# stm32hw03.net
KiCad netlist of a schematic drawn in EAGLE
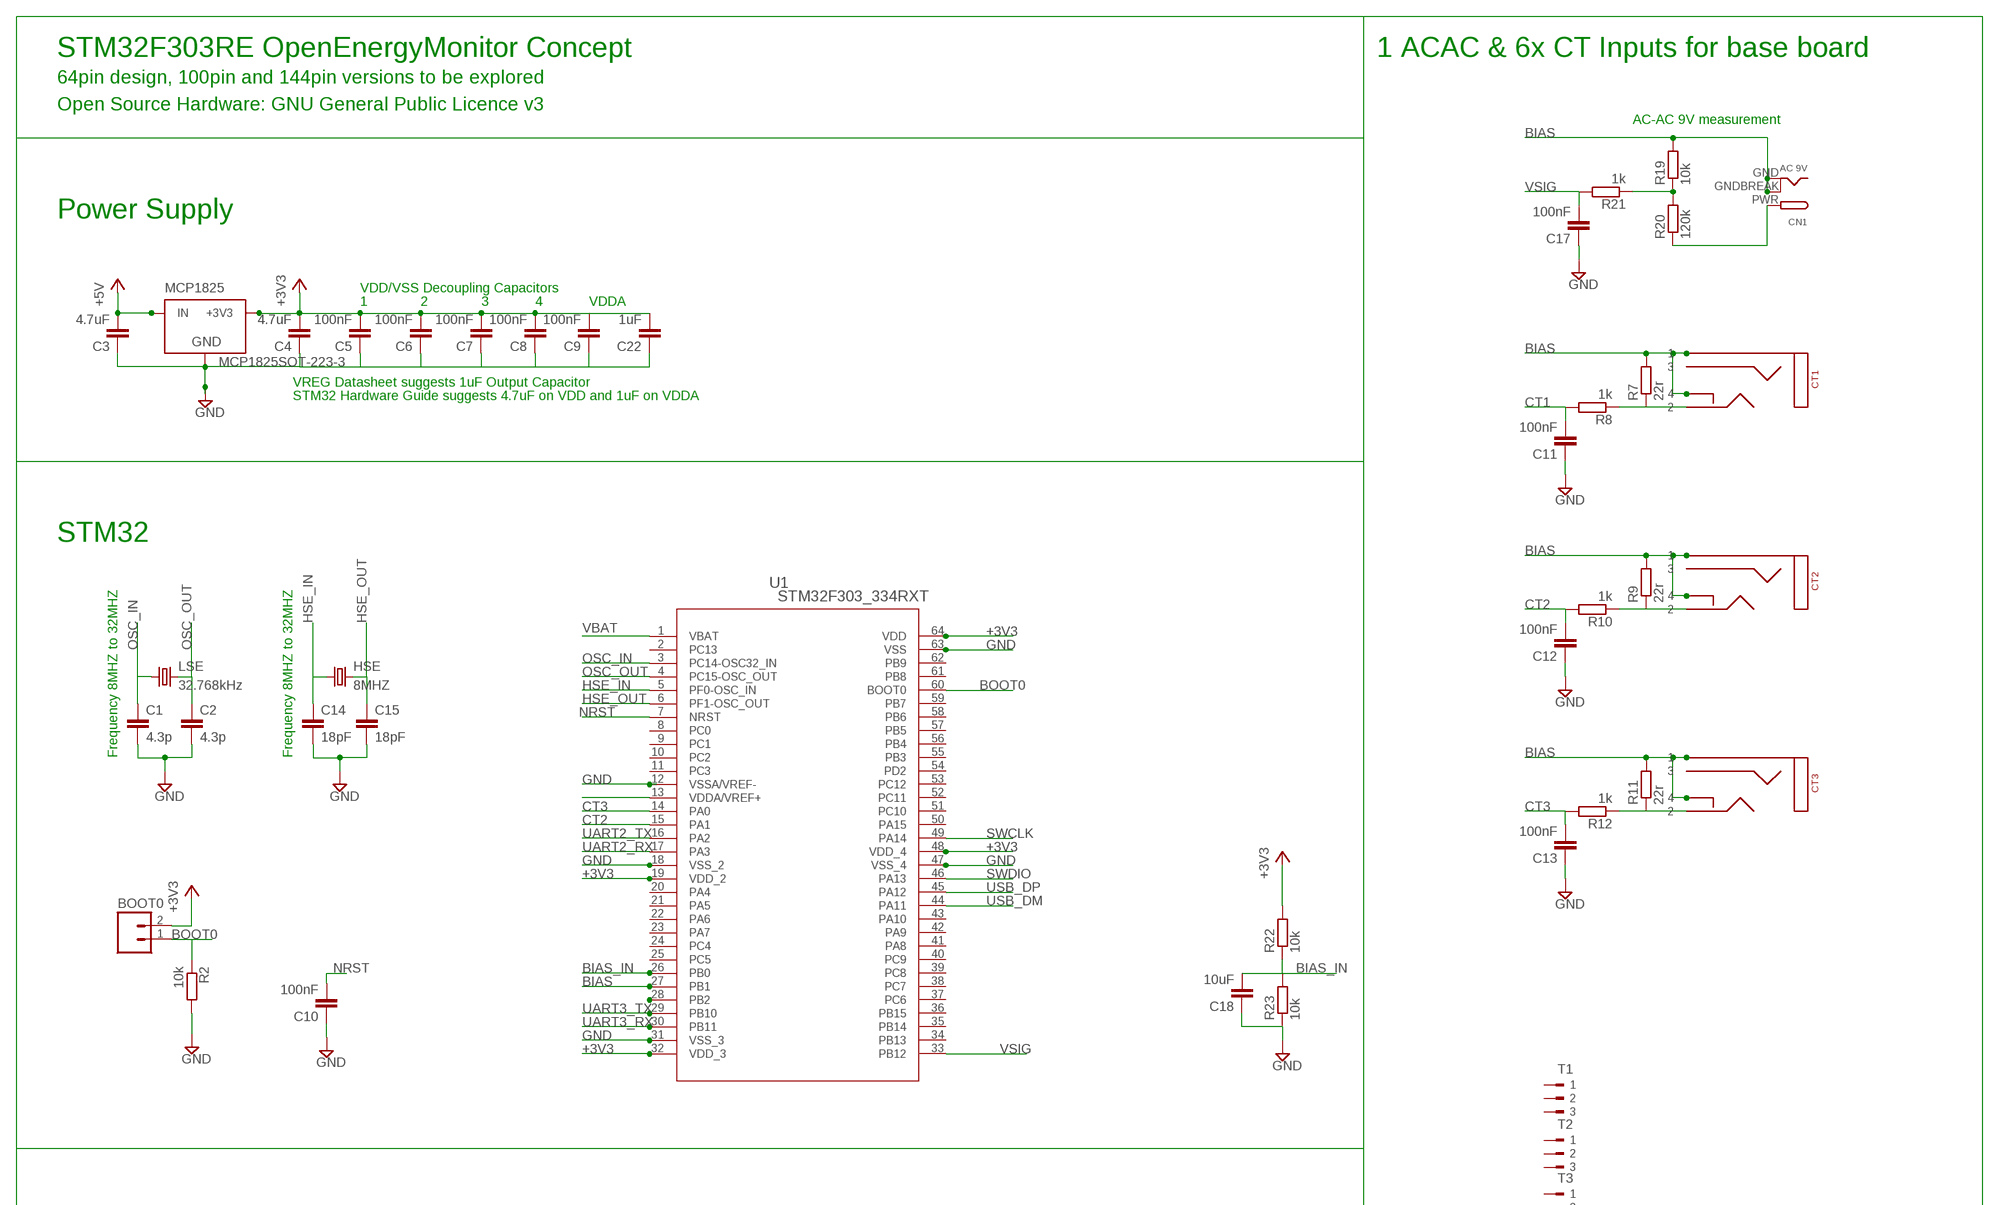
[diagram p0: schematic, sheet 1, part 1 of 2]
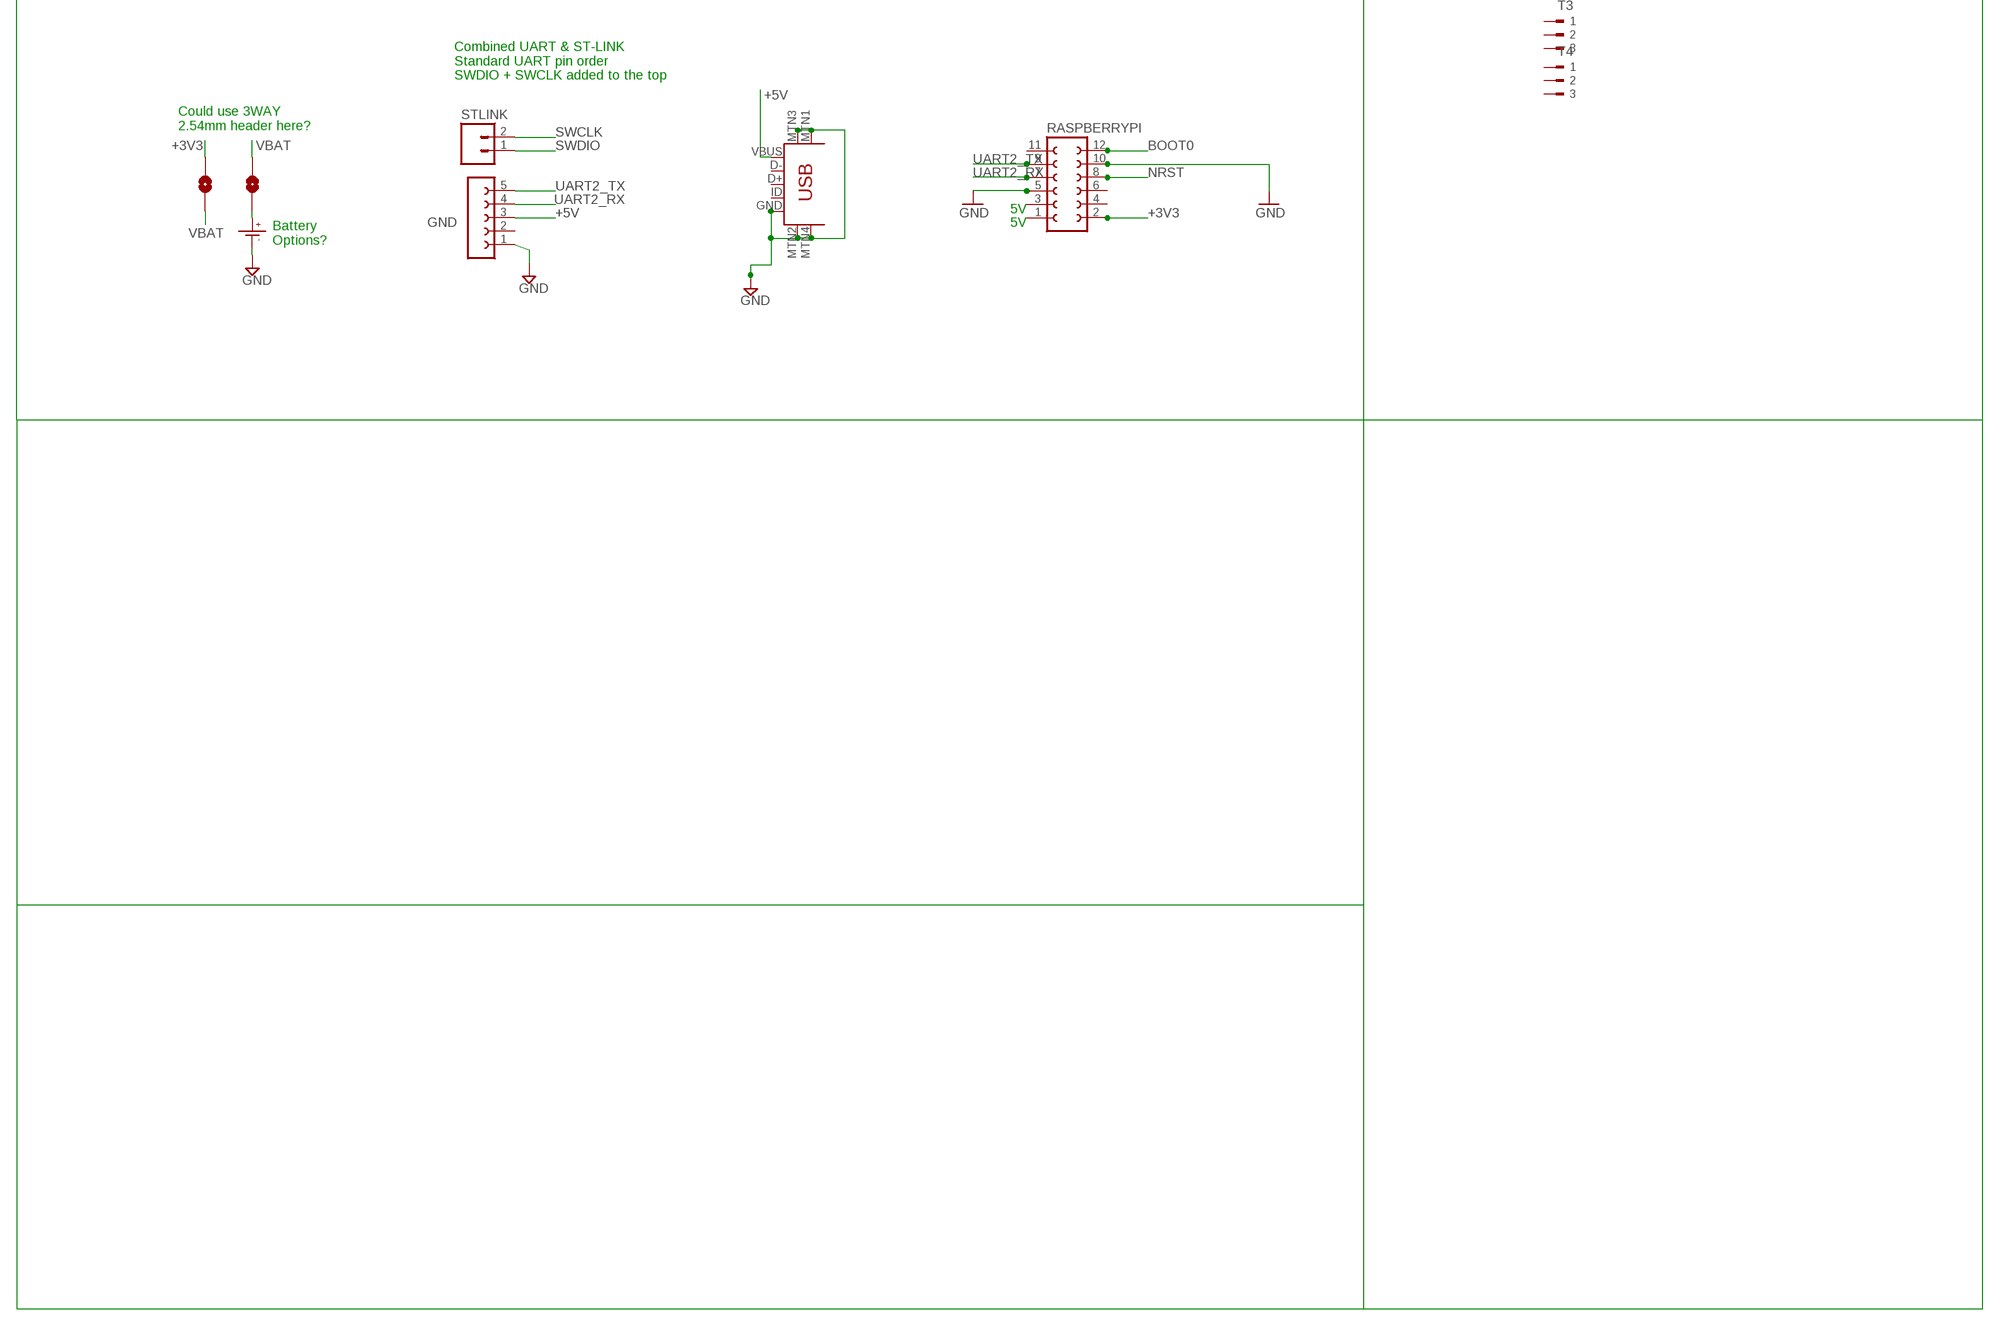
[diagram p1: schematic, sheet 1, part 2 of 2]

(export (version "E")
  (design (tool "Eeschema 10.0.6"))
  (components
    (comp (ref "3V3")
      (value "SOLDERJUMPERNO")
      (footprint "eagle-import:SJ_2S-NO")
      (libsource (lib "eagle-import") (part "SOLDERJUMPERNO"))
    )
    (comp (ref "BATTERY")
      (value "SOLDERJUMPERNO")
      (footprint "eagle-import:SJ_2S-NO")
      (libsource (lib "eagle-import") (part "SOLDERJUMPERNO"))
    )
    (comp (ref "BOOT0")
      (value "M02PTH")
      (footprint "eagle-import:1X02")
      (libsource (lib "eagle-import") (part "M02PTH"))
    )
    (comp (ref "C1")
      (value "4.3p")
      (footprint "eagle-import:C0603")
      (libsource (lib "eagle-import") (part "C-EUC0603"))
    )
    (comp (ref "C2")
      (value "4.3p")
      (footprint "eagle-import:C0603")
      (libsource (lib "eagle-import") (part "C-EUC0603"))
    )
    (comp (ref "C3")
      (value "4.7uF")
      (footprint "eagle-import:C0603")
      (libsource (lib "eagle-import") (part "C-EUC0603"))
    )
    (comp (ref "C4")
      (value "4.7uF")
      (footprint "eagle-import:C0603")
      (libsource (lib "eagle-import") (part "C-EUC0603"))
    )
    (comp (ref "C5")
      (value "100nF")
      (footprint "eagle-import:C0603")
      (libsource (lib "eagle-import") (part "C-EUC0603"))
    )
    (comp (ref "C6")
      (value "100nF")
      (footprint "eagle-import:C0603")
      (libsource (lib "eagle-import") (part "C-EUC0603"))
    )
    (comp (ref "C7")
      (value "100nF")
      (footprint "eagle-import:C0603")
      (libsource (lib "eagle-import") (part "C-EUC0603"))
    )
    (comp (ref "C8")
      (value "100nF")
      (footprint "eagle-import:C0603")
      (libsource (lib "eagle-import") (part "C-EUC0603"))
    )
    (comp (ref "C9")
      (value "100nF")
      (footprint "eagle-import:C0603")
      (libsource (lib "eagle-import") (part "C-EUC0603"))
    )
    (comp (ref "C10")
      (value "100nF")
      (footprint "eagle-import:C0603")
      (libsource (lib "eagle-import") (part "C-EUC0603"))
    )
    (comp (ref "C11")
      (value "100nF")
      (footprint "eagle-import:C0603")
      (libsource (lib "eagle-import") (part "C-EUC0603"))
    )
    (comp (ref "C12")
      (value "100nF")
      (footprint "eagle-import:C0603")
      (libsource (lib "eagle-import") (part "C-EUC0603"))
    )
    (comp (ref "C13")
      (value "100nF")
      (footprint "eagle-import:C0603")
      (libsource (lib "eagle-import") (part "C-EUC0603"))
    )
    (comp (ref "C14")
      (value "18pF")
      (footprint "eagle-import:C0603")
      (libsource (lib "eagle-import") (part "C-EUC0603"))
    )
    (comp (ref "C15")
      (value "18pF")
      (footprint "eagle-import:C0603")
      (libsource (lib "eagle-import") (part "C-EUC0603"))
    )
    (comp (ref "C17")
      (value "100nF")
      (footprint "eagle-import:C0603")
      (libsource (lib "eagle-import") (part "C-EUC0603"))
    )
    (comp (ref "C18")
      (value "10uF")
      (footprint "eagle-import:C0603")
      (libsource (lib "eagle-import") (part "C-EUC0603"))
    )
    (comp (ref "C22")
      (value "1uF")
      (footprint "eagle-import:C0603")
      (libsource (lib "eagle-import") (part "C-EUC0603"))
    )
    (comp (ref "CN1")
      (value "AC 9V")
      (footprint "eagle-import:DCJACK_2MM_PTH")
      (libsource (lib "eagle-import") (part "DCBARRELPTH"))
    )
    (comp (ref "CR1220")
      (value "CR1220SMD")
      (footprint "eagle-import:CR1220SMD")
      (fields (field (name "MPN") "Harwin S8411-45R"))
      (libsource (lib "eagle-import") (part "CR1220SMD"))
    )
    (comp (ref "CT1")
      (value "STEREO_SMD")
      (footprint "eagle-import:STEREO_SMT")
      (libsource (lib "eagle-import") (part "STEREO_SMD"))
    )
    (comp (ref "CT2")
      (value "STEREO_SMD")
      (footprint "eagle-import:STEREO_SMT")
      (libsource (lib "eagle-import") (part "STEREO_SMD"))
    )
    (comp (ref "CT3")
      (value "STEREO_SMD")
      (footprint "eagle-import:STEREO_SMT")
      (libsource (lib "eagle-import") (part "STEREO_SMD"))
    )
    (comp (ref "GND")
      (value "UART")
      (footprint "eagle-import:FE05-1")
      (libsource (lib "eagle-import") (part "FE05-1"))
    )
    (comp (ref "HSE")
      (value "8MHZ")
      (footprint "eagle-import:CTS406")
      (libsource (lib "eagle-import") (part "CRYSTALCTS406"))
    )
    (comp (ref "LSE")
      (value "32.768kHz")
      (footprint "eagle-import:MC-306")
      (fields (field (name "MPN") "MC-306 60.0KHZ  100PPM ,12.5PF"))
      (libsource (lib "eagle-import") (part "MC-306"))
    )
    (comp (ref "MCP1825")
      (value "MCP1825SOT-223-3")
      (footprint "eagle-import:SOT-223")
      (libsource (lib "eagle-import") (part "MCP1825SOT-223-3"))
    )
    (comp (ref "R2")
      (value "10k")
      (footprint "eagle-import:R0603")
      (libsource (lib "eagle-import") (part "R-EU_R0603"))
    )
    (comp (ref "R7")
      (value "22r")
      (footprint "eagle-import:R0603")
      (libsource (lib "eagle-import") (part "R-EU_R0603"))
    )
    (comp (ref "R8")
      (value "1k")
      (footprint "eagle-import:R0603")
      (libsource (lib "eagle-import") (part "R-EU_R0603"))
    )
    (comp (ref "R9")
      (value "22r")
      (footprint "eagle-import:R0603")
      (libsource (lib "eagle-import") (part "R-EU_R0603"))
    )
    (comp (ref "R10")
      (value "1k")
      (footprint "eagle-import:R0603")
      (libsource (lib "eagle-import") (part "R-EU_R0603"))
    )
    (comp (ref "R11")
      (value "22r")
      (footprint "eagle-import:R0603")
      (libsource (lib "eagle-import") (part "R-EU_R0603"))
    )
    (comp (ref "R12")
      (value "1k")
      (footprint "eagle-import:R0603")
      (libsource (lib "eagle-import") (part "R-EU_R0603"))
    )
    (comp (ref "R19")
      (value "10k")
      (footprint "eagle-import:R0603")
      (libsource (lib "eagle-import") (part "R-EU_R0603"))
    )
    (comp (ref "R20")
      (value "120k")
      (footprint "eagle-import:R0603")
      (libsource (lib "eagle-import") (part "R-EU_R0603"))
    )
    (comp (ref "R21")
      (value "1k")
      (footprint "eagle-import:R0603")
      (libsource (lib "eagle-import") (part "R-EU_R0603"))
    )
    (comp (ref "R22")
      (value "10k")
      (footprint "eagle-import:R0603")
      (libsource (lib "eagle-import") (part "R-EU_R0603"))
    )
    (comp (ref "R23")
      (value "10k")
      (footprint "eagle-import:R0603")
      (libsource (lib "eagle-import") (part "R-EU_R0603"))
    )
    (comp (ref "RASPBERRYPI")
      (value "FE06-2")
      (footprint "eagle-import:FE06-2")
      (libsource (lib "eagle-import") (part "FE06-2"))
    )
    (comp (ref "STLINK")
      (value "M02PTH")
      (footprint "eagle-import:1X02")
      (libsource (lib "eagle-import") (part "M02PTH"))
    )
    (comp (ref "T1")
      (value "180-3")
      (footprint "eagle-import:180-3")
      (libsource (lib "eagle-import") (part "180-3"))
    )
    (comp (ref "T2")
      (value "180-3")
      (footprint "eagle-import:180-3")
      (libsource (lib "eagle-import") (part "180-3"))
    )
    (comp (ref "T3")
      (value "180-3")
      (footprint "eagle-import:180-3")
      (libsource (lib "eagle-import") (part "180-3"))
    )
    (comp (ref "T4")
      (value "180-3")
      (footprint "eagle-import:180-3")
      (libsource (lib "eagle-import") (part "180-3"))
    )
    (comp (ref "U$10")
      (value "USB-MINIB-5PIN")
      (footprint "eagle-import:USB-MINIB-CISECO")
      (libsource (lib "eagle-import") (part "USB-MINIB-5PIN"))
    )
    (comp (ref "U1")
      (value "STM32F303_334RXT")
      (footprint "eagle-import:LQFP64-10X10MM")
      (fields (field (name "MANUFACTURER_PART_NUMBER") "stm32f303_334rxt"))
      (libsource (lib "eagle-import") (part "STM32F303_334RXT"))
    )
  )
  (nets
    (net (code "1") (name "+3V3") (class "Default")
      (node (ref "3V3") (pin "1") (pinfunction "1_1") (pintype "passive"))
      (node (ref "BOOT0") (pin "2") (pinfunction "2_2") (pintype "passive"))
      (node (ref "C22") (pin "2") (pinfunction "2_2") (pintype "passive"))
      (node (ref "C4") (pin "2") (pinfunction "2_2") (pintype "passive"))
      (node (ref "C5") (pin "2") (pinfunction "2_2") (pintype "passive"))
      (node (ref "C6") (pin "2") (pinfunction "2_2") (pintype "passive"))
      (node (ref "C7") (pin "2") (pinfunction "2_2") (pintype "passive"))
      (node (ref "C8") (pin "2") (pinfunction "2_2") (pintype "passive"))
      (node (ref "C9") (pin "2") (pinfunction "2_2") (pintype "passive"))
      (node (ref "MCP1825") (pin "3") (pinfunction "+3V3_3") (pintype "power_in"))
      (node (ref "R22") (pin "2") (pinfunction "2_2") (pintype "passive"))
      (node (ref "RASPBERRYPI") (pin "2") (pinfunction "2_2") (pintype "passive"))
      (node (ref "U1") (pin "13") (pinfunction "VDDA/VREF+_13") (pintype "power_in"))
      (node (ref "U1") (pin "19") (pinfunction "VDD_2_19") (pintype "power_in"))
      (node (ref "U1") (pin "32") (pinfunction "VDD_3_32") (pintype "power_in"))
      (node (ref "U1") (pin "48") (pinfunction "VDD_4_48") (pintype "power_in"))
      (node (ref "U1") (pin "64") (pinfunction "VDD_64") (pintype "power_in"))
    )
    (net (code "2") (name "+5V") (class "Default")
      (node (ref "C3") (pin "2") (pinfunction "2_2") (pintype "passive"))
      (node (ref "GND") (pin "3") (pinfunction "3_3") (pintype "passive"))
      (node (ref "MCP1825") (pin "1") (pinfunction "IN_1") (pintype "power_in"))
      (node (ref "U$10") (pin "VBUS") (pinfunction "VBUS_VBUS") (pintype "bidirectional"))
    )
    (net (code "3") (name "/BIAS") (class "Default")
      (node (ref "CN1") (pin "GND") (pinfunction "GND_GND") (pintype "power_in"))
      (node (ref "CN1") (pin "GNDBREAK") (pinfunction "GNDBREAK_GNDBREAK") (pintype "power_in"))
      (node (ref "CT1") (pin "P$1") (pinfunction "1_P$1") (pintype "bidirectional"))
      (node (ref "CT1") (pin "P$4") (pinfunction "4_P$4") (pintype "bidirectional"))
      (node (ref "CT2") (pin "P$1") (pinfunction "1_P$1") (pintype "bidirectional"))
      (node (ref "CT2") (pin "P$4") (pinfunction "4_P$4") (pintype "bidirectional"))
      (node (ref "CT3") (pin "P$1") (pinfunction "1_P$1") (pintype "bidirectional"))
      (node (ref "CT3") (pin "P$4") (pinfunction "4_P$4") (pintype "bidirectional"))
      (node (ref "R11") (pin "2") (pinfunction "2_2") (pintype "passive"))
      (node (ref "R19") (pin "2") (pinfunction "2_2") (pintype "passive"))
      (node (ref "R7") (pin "2") (pinfunction "2_2") (pintype "passive"))
      (node (ref "R9") (pin "2") (pinfunction "2_2") (pintype "passive"))
      (node (ref "U1") (pin "27") (pinfunction "PB1_27") (pintype "bidirectional"))
    )
    (net (code "4") (name "/BIAS_IN") (class "Default")
      (node (ref "C18") (pin "2") (pinfunction "2_2") (pintype "passive"))
      (node (ref "R22") (pin "1") (pinfunction "1_1") (pintype "passive"))
      (node (ref "R23") (pin "2") (pinfunction "2_2") (pintype "passive"))
      (node (ref "U1") (pin "26") (pinfunction "PB0_26") (pintype "bidirectional"))
    )
    (net (code "5") (name "/BOOT0") (class "Default")
      (node (ref "BOOT0") (pin "1") (pinfunction "1_1") (pintype "passive"))
      (node (ref "R2") (pin "1") (pinfunction "1_1") (pintype "passive"))
      (node (ref "RASPBERRYPI") (pin "12") (pinfunction "12_12") (pintype "passive"))
      (node (ref "U1") (pin "60") (pinfunction "BOOT0_60") (pintype "input"))
    )
    (net (code "6") (name "/CT1") (class "Default")
      (node (ref "C11") (pin "2") (pinfunction "2_2") (pintype "passive"))
      (node (ref "R8") (pin "2") (pinfunction "2_2") (pintype "passive"))
    )
    (net (code "7") (name "/CT2") (class "Default")
      (node (ref "C12") (pin "2") (pinfunction "2_2") (pintype "passive"))
      (node (ref "R10") (pin "2") (pinfunction "2_2") (pintype "passive"))
      (node (ref "U1") (pin "15") (pinfunction "PA1_15") (pintype "bidirectional"))
    )
    (net (code "8") (name "/CT3") (class "Default")
      (node (ref "C13") (pin "2") (pinfunction "2_2") (pintype "passive"))
      (node (ref "R12") (pin "2") (pinfunction "2_2") (pintype "passive"))
      (node (ref "U1") (pin "14") (pinfunction "PA0_14") (pintype "bidirectional"))
    )
    (net (code "9") (name "/HSE_IN") (class "Default")
      (node (ref "C14") (pin "1") (pinfunction "1_1") (pintype "passive"))
      (node (ref "HSE") (pin "1") (pinfunction "1_1") (pintype "passive"))
      (node (ref "U1") (pin "5") (pinfunction "PF0-OSC_IN_5") (pintype "bidirectional"))
    )
    (net (code "10") (name "/HSE_OUT") (class "Default")
      (node (ref "C15") (pin "1") (pinfunction "1_1") (pintype "passive"))
      (node (ref "HSE") (pin "3") (pinfunction "2_3") (pintype "passive"))
      (node (ref "U1") (pin "6") (pinfunction "PF1-OSC_OUT_6") (pintype "bidirectional"))
    )
    (net (code "11") (name "/NRST") (class "Default")
      (node (ref "C10") (pin "2") (pinfunction "2_2") (pintype "passive"))
      (node (ref "RASPBERRYPI") (pin "8") (pinfunction "8_8") (pintype "passive"))
      (node (ref "U1") (pin "7") (pinfunction "NRST_7") (pintype "bidirectional"))
    )
    (net (code "12") (name "/OSC_IN") (class "Default")
      (node (ref "C1") (pin "1") (pinfunction "1_1") (pintype "passive"))
      (node (ref "LSE") (pin "1") (pinfunction "1_1") (pintype "passive"))
      (node (ref "U1") (pin "3") (pinfunction "PC14-OSC32_IN_3") (pintype "bidirectional"))
    )
    (net (code "13") (name "/OSC_OUT") (class "Default")
      (node (ref "C2") (pin "1") (pinfunction "1_1") (pintype "passive"))
      (node (ref "LSE") (pin "4") (pinfunction "2_4") (pintype "passive"))
      (node (ref "U1") (pin "4") (pinfunction "PC15-OSC_OUT_4") (pintype "bidirectional"))
    )
    (net (code "14") (name "/SWCLK") (class "Default")
      (node (ref "STLINK") (pin "2") (pinfunction "2_2") (pintype "passive"))
      (node (ref "U1") (pin "49") (pinfunction "PA14_49") (pintype "bidirectional"))
    )
    (net (code "15") (name "/SWDIO") (class "Default")
      (node (ref "STLINK") (pin "1") (pinfunction "1_1") (pintype "passive"))
      (node (ref "U1") (pin "46") (pinfunction "PA13_46") (pintype "bidirectional"))
    )
    (net (code "16") (name "/UART2_RX") (class "Default")
      (node (ref "GND") (pin "4") (pinfunction "4_4") (pintype "passive"))
      (node (ref "RASPBERRYPI") (pin "7") (pinfunction "7_7") (pintype "passive"))
      (node (ref "U1") (pin "17") (pinfunction "PA3_17") (pintype "bidirectional"))
    )
    (net (code "17") (name "/UART2_TX") (class "Default")
      (node (ref "GND") (pin "5") (pinfunction "5_5") (pintype "passive"))
      (node (ref "RASPBERRYPI") (pin "9") (pinfunction "9_9") (pintype "passive"))
      (node (ref "U1") (pin "16") (pinfunction "PA2_16") (pintype "bidirectional"))
    )
    (net (code "18") (name "/UART3_RX") (class "Default")
      (node (ref "U1") (pin "30") (pinfunction "PB11_30") (pintype "bidirectional"))
    )
    (net (code "19") (name "/UART3_TX") (class "Default")
      (node (ref "U1") (pin "29") (pinfunction "PB10_29") (pintype "bidirectional"))
    )
    (net (code "20") (name "/USB_DM") (class "Default")
      (node (ref "U1") (pin "44") (pinfunction "PA11_44") (pintype "bidirectional"))
    )
    (net (code "21") (name "/USB_DP") (class "Default")
      (node (ref "U1") (pin "45") (pinfunction "PA12_45") (pintype "bidirectional"))
    )
    (net (code "22") (name "/VBAT") (class "Default")
      (node (ref "3V3") (pin "2") (pinfunction "2_2") (pintype "passive"))
      (node (ref "BATTERY") (pin "1") (pinfunction "1_1") (pintype "passive"))
      (node (ref "U1") (pin "1") (pinfunction "VBAT_1") (pintype "power_in"))
    )
    (net (code "23") (name "/VSIG") (class "Default")
      (node (ref "C17") (pin "2") (pinfunction "2_2") (pintype "passive"))
      (node (ref "R21") (pin "2") (pinfunction "2_2") (pintype "passive"))
      (node (ref "U1") (pin "33") (pinfunction "PB12_33") (pintype "bidirectional"))
    )
    (net (code "24") (name "GND") (class "Default")
      (node (ref "C1") (pin "2") (pinfunction "2_2") (pintype "passive"))
      (node (ref "C10") (pin "1") (pinfunction "1_1") (pintype "passive"))
      (node (ref "C11") (pin "1") (pinfunction "1_1") (pintype "passive"))
      (node (ref "C12") (pin "1") (pinfunction "1_1") (pintype "passive"))
      (node (ref "C13") (pin "1") (pinfunction "1_1") (pintype "passive"))
      (node (ref "C14") (pin "2") (pinfunction "2_2") (pintype "passive"))
      (node (ref "C15") (pin "2") (pinfunction "2_2") (pintype "passive"))
      (node (ref "C17") (pin "1") (pinfunction "1_1") (pintype "passive"))
      (node (ref "C18") (pin "1") (pinfunction "1_1") (pintype "passive"))
      (node (ref "C2") (pin "2") (pinfunction "2_2") (pintype "passive"))
      (node (ref "C22") (pin "1") (pinfunction "1_1") (pintype "passive"))
      (node (ref "C3") (pin "1") (pinfunction "1_1") (pintype "passive"))
      (node (ref "C4") (pin "1") (pinfunction "1_1") (pintype "passive"))
      (node (ref "C5") (pin "1") (pinfunction "1_1") (pintype "passive"))
      (node (ref "C6") (pin "1") (pinfunction "1_1") (pintype "passive"))
      (node (ref "C7") (pin "1") (pinfunction "1_1") (pintype "passive"))
      (node (ref "C8") (pin "1") (pinfunction "1_1") (pintype "passive"))
      (node (ref "C9") (pin "1") (pinfunction "1_1") (pintype "passive"))
      (node (ref "CR1220") (pin "P-") (pinfunction "P$-_P-") (pintype "bidirectional"))
      (node (ref "GND") (pin "1") (pinfunction "1_1") (pintype "passive"))
      (node (ref "MCP1825") (pin "2") (pinfunction "GND_2") (pintype "power_in"))
      (node (ref "R2") (pin "2") (pinfunction "2_2") (pintype "passive"))
      (node (ref "R23") (pin "1") (pinfunction "1_1") (pintype "passive"))
      (node (ref "RASPBERRYPI") (pin "10") (pinfunction "10_10") (pintype "passive"))
      (node (ref "RASPBERRYPI") (pin "5") (pinfunction "5_5") (pintype "passive"))
      (node (ref "U$10") (pin "GND") (pinfunction "GND_GND") (pintype "bidirectional"))
      (node (ref "U$10") (pin "MTN1") (pinfunction "MTN2_MTN1") (pintype "bidirectional"))
      (node (ref "U$10") (pin "MTN2") (pinfunction "MTN3_MTN2") (pintype "bidirectional"))
      (node (ref "U$10") (pin "MTN3") (pinfunction "MTN1_MTN3") (pintype "bidirectional"))
      (node (ref "U$10") (pin "MTN4") (pinfunction "MTN4_MTN4") (pintype "bidirectional"))
      (node (ref "U1") (pin "12") (pinfunction "VSSA/VREF-_12") (pintype "power_in"))
      (node (ref "U1") (pin "18") (pinfunction "VSS_2_18") (pintype "power_in"))
      (node (ref "U1") (pin "31") (pinfunction "VSS_3_31") (pintype "power_in"))
      (node (ref "U1") (pin "47") (pinfunction "VSS_4_47") (pintype "power_in"))
      (node (ref "U1") (pin "63") (pinfunction "VSS_63") (pintype "power_in"))
    )
    (net (code "25") (name "Net-(CN1-PadPWR)") (class "Default")
      (node (ref "CN1") (pin "PWR") (pinfunction "PWR_PWR") (pintype "power_in"))
      (node (ref "R20") (pin "1") (pinfunction "1_1") (pintype "passive"))
    )
    (net (code "26") (name "Net-(CR1220-P$+)") (class "Default")
      (node (ref "BATTERY") (pin "2") (pinfunction "2_2") (pintype "passive"))
      (node (ref "CR1220") (pin "P+") (pinfunction "P$+_P+") (pintype "bidirectional"))
    )
    (net (code "27") (name "Net-(CT1-2)") (class "Default")
      (node (ref "CT1") (pin "P$2") (pinfunction "2_P$2") (pintype "bidirectional"))
      (node (ref "R7") (pin "1") (pinfunction "1_1") (pintype "passive"))
      (node (ref "R8") (pin "1") (pinfunction "1_1") (pintype "passive"))
    )
    (net (code "28") (name "Net-(CT2-2)") (class "Default")
      (node (ref "CT2") (pin "P$2") (pinfunction "2_P$2") (pintype "bidirectional"))
      (node (ref "R10") (pin "1") (pinfunction "1_1") (pintype "passive"))
      (node (ref "R9") (pin "1") (pinfunction "1_1") (pintype "passive"))
    )
    (net (code "29") (name "Net-(CT3-2)") (class "Default")
      (node (ref "CT3") (pin "P$2") (pinfunction "2_P$2") (pintype "bidirectional"))
      (node (ref "R11") (pin "1") (pinfunction "1_1") (pintype "passive"))
      (node (ref "R12") (pin "1") (pinfunction "1_1") (pintype "passive"))
    )
    (net (code "30") (name "Net-(R19-Pad1)") (class "Default")
      (node (ref "R19") (pin "1") (pinfunction "1_1") (pintype "passive"))
      (node (ref "R20") (pin "2") (pinfunction "2_2") (pintype "passive"))
      (node (ref "R21") (pin "1") (pinfunction "1_1") (pintype "passive"))
    )
    (net (code "31") (name "unconnected-(CT1-3-PadP$3)") (class "Default")
      (node (ref "CT1") (pin "P$3") (pinfunction "3_P$3") (pintype "bidirectional"))
    )
    (net (code "32") (name "unconnected-(CT2-3-PadP$3)") (class "Default")
      (node (ref "CT2") (pin "P$3") (pinfunction "3_P$3") (pintype "bidirectional"))
    )
    (net (code "33") (name "unconnected-(CT3-3-PadP$3)") (class "Default")
      (node (ref "CT3") (pin "P$3") (pinfunction "3_P$3") (pintype "bidirectional"))
    )
    (net (code "34") (name "unconnected-(GND-Pad2)") (class "Default")
      (node (ref "GND") (pin "2") (pinfunction "2_2") (pintype "passive"))
    )
    (net (code "35") (name "unconnected-(RASPBERRYPI-Pad1)") (class "Default")
      (node (ref "RASPBERRYPI") (pin "1") (pinfunction "1_1") (pintype "passive"))
    )
    (net (code "36") (name "unconnected-(RASPBERRYPI-Pad3)") (class "Default")
      (node (ref "RASPBERRYPI") (pin "3") (pinfunction "3_3") (pintype "passive"))
    )
    (net (code "37") (name "unconnected-(RASPBERRYPI-Pad4)") (class "Default")
      (node (ref "RASPBERRYPI") (pin "4") (pinfunction "4_4") (pintype "passive"))
    )
    (net (code "38") (name "unconnected-(RASPBERRYPI-Pad6)") (class "Default")
      (node (ref "RASPBERRYPI") (pin "6") (pinfunction "6_6") (pintype "passive"))
    )
    (net (code "39") (name "unconnected-(RASPBERRYPI-Pad11)") (class "Default")
      (node (ref "RASPBERRYPI") (pin "11") (pinfunction "11_11") (pintype "passive"))
    )
    (net (code "40") (name "unconnected-(T1-Pad1)") (class "Default")
      (node (ref "T1") (pin "1") (pinfunction "1_1") (pintype "passive"))
    )
    (net (code "41") (name "unconnected-(T1-Pad2)") (class "Default")
      (node (ref "T1") (pin "2") (pinfunction "2_2") (pintype "passive"))
    )
    (net (code "42") (name "unconnected-(T1-Pad3)") (class "Default")
      (node (ref "T1") (pin "3") (pinfunction "3_3") (pintype "passive"))
    )
    (net (code "43") (name "unconnected-(T2-Pad1)") (class "Default")
      (node (ref "T2") (pin "1") (pinfunction "1_1") (pintype "passive"))
    )
    (net (code "44") (name "unconnected-(T2-Pad2)") (class "Default")
      (node (ref "T2") (pin "2") (pinfunction "2_2") (pintype "passive"))
    )
    (net (code "45") (name "unconnected-(T2-Pad3)") (class "Default")
      (node (ref "T2") (pin "3") (pinfunction "3_3") (pintype "passive"))
    )
    (net (code "46") (name "unconnected-(T3-Pad1)") (class "Default")
      (node (ref "T3") (pin "1") (pinfunction "1_1") (pintype "passive"))
    )
    (net (code "47") (name "unconnected-(T3-Pad2)") (class "Default")
      (node (ref "T3") (pin "2") (pinfunction "2_2") (pintype "passive"))
    )
    (net (code "48") (name "unconnected-(T3-Pad3)") (class "Default")
      (node (ref "T3") (pin "3") (pinfunction "3_3") (pintype "passive"))
    )
    (net (code "49") (name "unconnected-(T4-Pad1)") (class "Default")
      (node (ref "T4") (pin "1") (pinfunction "1_1") (pintype "passive"))
    )
    (net (code "50") (name "unconnected-(T4-Pad2)") (class "Default")
      (node (ref "T4") (pin "2") (pinfunction "2_2") (pintype "passive"))
    )
    (net (code "51") (name "unconnected-(T4-Pad3)") (class "Default")
      (node (ref "T4") (pin "3") (pinfunction "3_3") (pintype "passive"))
    )
    (net (code "52") (name "unconnected-(U$10-PadD+)") (class "Default")
      (node (ref "U$10") (pin "D+") (pinfunction "D+_D+") (pintype "bidirectional"))
    )
    (net (code "53") (name "unconnected-(U$10-PadD-)") (class "Default")
      (node (ref "U$10") (pin "D-") (pinfunction "D-_D-") (pintype "bidirectional"))
    )
    (net (code "54") (name "unconnected-(U$10-PadID)") (class "Default")
      (node (ref "U$10") (pin "ID") (pinfunction "ID_ID") (pintype "bidirectional"))
    )
    (net (code "55") (name "unconnected-(U1-PA4-Pad20)") (class "Default")
      (node (ref "U1") (pin "20") (pinfunction "PA4_20") (pintype "bidirectional"))
    )
    (net (code "56") (name "unconnected-(U1-PA5-Pad21)") (class "Default")
      (node (ref "U1") (pin "21") (pinfunction "PA5_21") (pintype "bidirectional"))
    )
    (net (code "57") (name "unconnected-(U1-PA6-Pad22)") (class "Default")
      (node (ref "U1") (pin "22") (pinfunction "PA6_22") (pintype "bidirectional"))
    )
    (net (code "58") (name "unconnected-(U1-PA7-Pad23)") (class "Default")
      (node (ref "U1") (pin "23") (pinfunction "PA7_23") (pintype "bidirectional"))
    )
    (net (code "59") (name "unconnected-(U1-PA8-Pad41)") (class "Default")
      (node (ref "U1") (pin "41") (pinfunction "PA8_41") (pintype "bidirectional"))
    )
    (net (code "60") (name "unconnected-(U1-PA9-Pad42)") (class "Default")
      (node (ref "U1") (pin "42") (pinfunction "PA9_42") (pintype "bidirectional"))
    )
    (net (code "61") (name "unconnected-(U1-PA10-Pad43)") (class "Default")
      (node (ref "U1") (pin "43") (pinfunction "PA10_43") (pintype "bidirectional"))
    )
    (net (code "62") (name "unconnected-(U1-PA15-Pad50)") (class "Default")
      (node (ref "U1") (pin "50") (pinfunction "PA15_50") (pintype "bidirectional"))
    )
    (net (code "63") (name "unconnected-(U1-PB2-Pad28)") (class "Default")
      (node (ref "U1") (pin "28") (pinfunction "PB2_28") (pintype "bidirectional"))
    )
    (net (code "64") (name "unconnected-(U1-PB3-Pad55)") (class "Default")
      (node (ref "U1") (pin "55") (pinfunction "PB3_55") (pintype "bidirectional"))
    )
    (net (code "65") (name "unconnected-(U1-PB4-Pad56)") (class "Default")
      (node (ref "U1") (pin "56") (pinfunction "PB4_56") (pintype "bidirectional"))
    )
    (net (code "66") (name "unconnected-(U1-PB5-Pad57)") (class "Default")
      (node (ref "U1") (pin "57") (pinfunction "PB5_57") (pintype "bidirectional"))
    )
    (net (code "67") (name "unconnected-(U1-PB6-Pad58)") (class "Default")
      (node (ref "U1") (pin "58") (pinfunction "PB6_58") (pintype "bidirectional"))
    )
    (net (code "68") (name "unconnected-(U1-PB7-Pad59)") (class "Default")
      (node (ref "U1") (pin "59") (pinfunction "PB7_59") (pintype "bidirectional"))
    )
    (net (code "69") (name "unconnected-(U1-PB8-Pad61)") (class "Default")
      (node (ref "U1") (pin "61") (pinfunction "PB8_61") (pintype "bidirectional"))
    )
    (net (code "70") (name "unconnected-(U1-PB9-Pad62)") (class "Default")
      (node (ref "U1") (pin "62") (pinfunction "PB9_62") (pintype "bidirectional"))
    )
    (net (code "71") (name "unconnected-(U1-PB13-Pad34)") (class "Default")
      (node (ref "U1") (pin "34") (pinfunction "PB13_34") (pintype "bidirectional"))
    )
    (net (code "72") (name "unconnected-(U1-PB14-Pad35)") (class "Default")
      (node (ref "U1") (pin "35") (pinfunction "PB14_35") (pintype "bidirectional"))
    )
    (net (code "73") (name "unconnected-(U1-PB15-Pad36)") (class "Default")
      (node (ref "U1") (pin "36") (pinfunction "PB15_36") (pintype "bidirectional"))
    )
    (net (code "74") (name "unconnected-(U1-PC0-Pad8)") (class "Default")
      (node (ref "U1") (pin "8") (pinfunction "PC0_8") (pintype "bidirectional"))
    )
    (net (code "75") (name "unconnected-(U1-PC1-Pad9)") (class "Default")
      (node (ref "U1") (pin "9") (pinfunction "PC1_9") (pintype "bidirectional"))
    )
    (net (code "76") (name "unconnected-(U1-PC2-Pad10)") (class "Default")
      (node (ref "U1") (pin "10") (pinfunction "PC2_10") (pintype "bidirectional"))
    )
    (net (code "77") (name "unconnected-(U1-PC3-Pad11)") (class "Default")
      (node (ref "U1") (pin "11") (pinfunction "PC3_11") (pintype "bidirectional"))
    )
    (net (code "78") (name "unconnected-(U1-PC4-Pad24)") (class "Default")
      (node (ref "U1") (pin "24") (pinfunction "PC4_24") (pintype "bidirectional"))
    )
    (net (code "79") (name "unconnected-(U1-PC5-Pad25)") (class "Default")
      (node (ref "U1") (pin "25") (pinfunction "PC5_25") (pintype "bidirectional"))
    )
    (net (code "80") (name "unconnected-(U1-PC6-Pad37)") (class "Default")
      (node (ref "U1") (pin "37") (pinfunction "PC6_37") (pintype "bidirectional"))
    )
    (net (code "81") (name "unconnected-(U1-PC7-Pad38)") (class "Default")
      (node (ref "U1") (pin "38") (pinfunction "PC7_38") (pintype "bidirectional"))
    )
    (net (code "82") (name "unconnected-(U1-PC8-Pad39)") (class "Default")
      (node (ref "U1") (pin "39") (pinfunction "PC8_39") (pintype "bidirectional"))
    )
    (net (code "83") (name "unconnected-(U1-PC9-Pad40)") (class "Default")
      (node (ref "U1") (pin "40") (pinfunction "PC9_40") (pintype "bidirectional"))
    )
    (net (code "84") (name "unconnected-(U1-PC10-Pad51)") (class "Default")
      (node (ref "U1") (pin "51") (pinfunction "PC10_51") (pintype "bidirectional"))
    )
    (net (code "85") (name "unconnected-(U1-PC11-Pad52)") (class "Default")
      (node (ref "U1") (pin "52") (pinfunction "PC11_52") (pintype "bidirectional"))
    )
    (net (code "86") (name "unconnected-(U1-PC12-Pad53)") (class "Default")
      (node (ref "U1") (pin "53") (pinfunction "PC12_53") (pintype "bidirectional"))
    )
    (net (code "87") (name "unconnected-(U1-PC13-Pad2)") (class "Default")
      (node (ref "U1") (pin "2") (pinfunction "PC13_2") (pintype "bidirectional"))
    )
    (net (code "88") (name "unconnected-(U1-PD2-Pad54)") (class "Default")
      (node (ref "U1") (pin "54") (pinfunction "PD2_54") (pintype "bidirectional"))
    )
  )
)
